# PCB_design.net
KiCad netlist of a schematic drawn in EAGLE
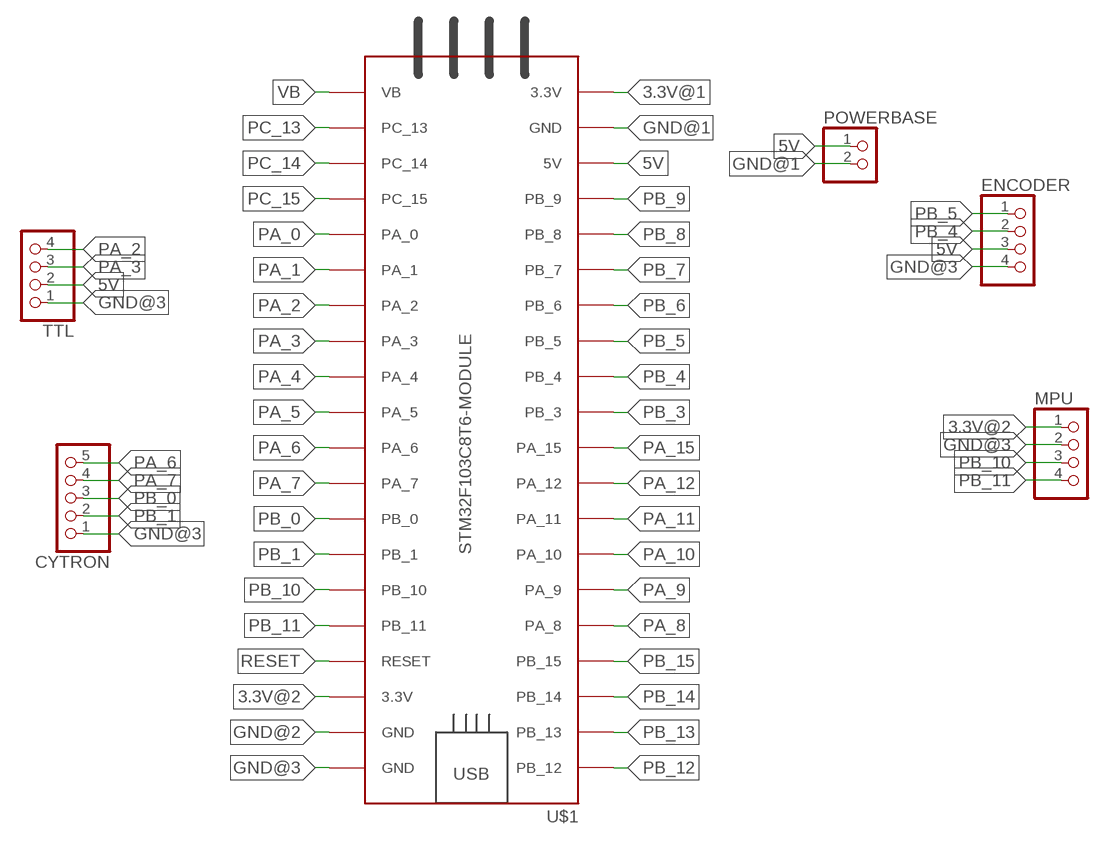
[diagram p0: schematic, sheet 1]

(export (version "E")
  (design (tool "Eeschema 10.0.6"))
  (components
    (comp (ref "CYTRON")
      (value "PINHD-1X5")
      (footprint "eagle-import:1X05")
      (libsource (lib "eagle-import") (part "PINHD-1X5"))
    )
    (comp (ref "ENCODER")
      (value "PINHD-1X4")
      (footprint "eagle-import:1X04")
      (libsource (lib "eagle-import") (part "PINHD-1X4"))
    )
    (comp (ref "MPU")
      (value "PINHD-1X4")
      (footprint "eagle-import:1X04")
      (libsource (lib "eagle-import") (part "PINHD-1X4"))
    )
    (comp (ref "POWERBASE")
      (value "PINHD-1X2")
      (footprint "eagle-import:1X02")
      (libsource (lib "eagle-import") (part "PINHD-1X2"))
    )
    (comp (ref "TTL")
      (value "PINHD-1X4")
      (footprint "eagle-import:1X04")
      (libsource (lib "eagle-import") (part "PINHD-1X4"))
    )
    (comp (ref "U$1")
      (value "STM32F103C8T6-MODULE")
      (footprint "eagle-import:STM32F103C8T6-MODULE")
      (libsource (lib "eagle-import") (part "STM32F103C8T6-MODULE"))
    )
  )
  (nets
    (net (code "1") (name "3.3V@1") (class "Default")
      (node (ref "U$1") (pin "3.3V_1") (pinfunction "3.3V_3.3V_1") (pintype "bidirectional"))
    )
    (net (code "2") (name "3.3V@2") (class "Default")
      (node (ref "MPU") (pin "1") (pinfunction "1_1") (pintype "passive"))
      (node (ref "U$1") (pin "3.3V_2") (pinfunction "3.3V_3.3V_2") (pintype "bidirectional"))
    )
    (net (code "3") (name "5V") (class "Default")
      (node (ref "ENCODER") (pin "3") (pinfunction "3_3") (pintype "passive"))
      (node (ref "POWERBASE") (pin "1") (pinfunction "1_1") (pintype "passive"))
      (node (ref "TTL") (pin "2") (pinfunction "2_2") (pintype "passive"))
      (node (ref "U$1") (pin "5V") (pinfunction "5V_5V") (pintype "bidirectional"))
    )
    (net (code "4") (name "GND@1") (class "Default")
      (node (ref "POWERBASE") (pin "2") (pinfunction "2_2") (pintype "passive"))
      (node (ref "U$1") (pin "GND_1") (pinfunction "GND_GND_1") (pintype "bidirectional"))
    )
    (net (code "5") (name "GND@2") (class "Default")
      (node (ref "U$1") (pin "GND_2") (pinfunction "GND_GND_2") (pintype "bidirectional"))
    )
    (net (code "6") (name "GND@3") (class "Default")
      (node (ref "CYTRON") (pin "1") (pinfunction "1_1") (pintype "passive"))
      (node (ref "ENCODER") (pin "4") (pinfunction "4_4") (pintype "passive"))
      (node (ref "MPU") (pin "2") (pinfunction "2_2") (pintype "passive"))
      (node (ref "TTL") (pin "1") (pinfunction "1_1") (pintype "passive"))
      (node (ref "U$1") (pin "GND_3") (pinfunction "GND_GND_3") (pintype "power_in"))
    )
    (net (code "7") (name "PA_0") (class "Default")
      (node (ref "U$1") (pin "PA_0") (pinfunction "PA_0_PA_0") (pintype "bidirectional"))
    )
    (net (code "8") (name "PA_1") (class "Default")
      (node (ref "U$1") (pin "PA_1") (pinfunction "PA_1_PA_1") (pintype "bidirectional"))
    )
    (net (code "9") (name "PA_2") (class "Default")
      (node (ref "TTL") (pin "4") (pinfunction "4_4") (pintype "passive"))
      (node (ref "U$1") (pin "PA_2") (pinfunction "PA_2_PA_2") (pintype "bidirectional"))
    )
    (net (code "10") (name "PA_3") (class "Default")
      (node (ref "TTL") (pin "3") (pinfunction "3_3") (pintype "passive"))
      (node (ref "U$1") (pin "PA_3") (pinfunction "PA_3_PA_3") (pintype "bidirectional"))
    )
    (net (code "11") (name "PA_4") (class "Default")
      (node (ref "U$1") (pin "PA_4") (pinfunction "PA_4_PA_4") (pintype "bidirectional"))
    )
    (net (code "12") (name "PA_5") (class "Default")
      (node (ref "U$1") (pin "PA_5") (pinfunction "PA_5_PA_5") (pintype "bidirectional"))
    )
    (net (code "13") (name "PA_6") (class "Default")
      (node (ref "CYTRON") (pin "5") (pinfunction "5_5") (pintype "passive"))
      (node (ref "U$1") (pin "PA_6") (pinfunction "PA_6_PA_6") (pintype "bidirectional"))
    )
    (net (code "14") (name "PA_7") (class "Default")
      (node (ref "CYTRON") (pin "4") (pinfunction "4_4") (pintype "passive"))
      (node (ref "U$1") (pin "PA_7") (pinfunction "PA_7_PA_7") (pintype "bidirectional"))
    )
    (net (code "15") (name "PA_8") (class "Default")
      (node (ref "U$1") (pin "PA_8") (pinfunction "PA_8_PA_8") (pintype "bidirectional"))
    )
    (net (code "16") (name "PA_9") (class "Default")
      (node (ref "U$1") (pin "PA_9") (pinfunction "PA_9_PA_9") (pintype "bidirectional"))
    )
    (net (code "17") (name "PA_10") (class "Default")
      (node (ref "U$1") (pin "PA_10") (pinfunction "PA_10_PA_10") (pintype "bidirectional"))
    )
    (net (code "18") (name "PA_11") (class "Default")
      (node (ref "U$1") (pin "PA_11") (pinfunction "PA_11_PA_11") (pintype "bidirectional"))
    )
    (net (code "19") (name "PA_12") (class "Default")
      (node (ref "U$1") (pin "PA_12") (pinfunction "PA_12_PA_12") (pintype "bidirectional"))
    )
    (net (code "20") (name "PA_15") (class "Default")
      (node (ref "U$1") (pin "PA_15") (pinfunction "PA_15_PA_15") (pintype "bidirectional"))
    )
    (net (code "21") (name "PB_0") (class "Default")
      (node (ref "CYTRON") (pin "3") (pinfunction "3_3") (pintype "passive"))
      (node (ref "U$1") (pin "PB_0") (pinfunction "PB_0_PB_0") (pintype "bidirectional"))
    )
    (net (code "22") (name "PB_1") (class "Default")
      (node (ref "CYTRON") (pin "2") (pinfunction "2_2") (pintype "passive"))
      (node (ref "U$1") (pin "PB_1") (pinfunction "PB_1_PB_1") (pintype "bidirectional"))
    )
    (net (code "23") (name "PB_3") (class "Default")
      (node (ref "U$1") (pin "PB_3") (pinfunction "PB_3_PB_3") (pintype "bidirectional"))
    )
    (net (code "24") (name "PB_4") (class "Default")
      (node (ref "ENCODER") (pin "2") (pinfunction "2_2") (pintype "passive"))
      (node (ref "U$1") (pin "PB_4") (pinfunction "PB_4_PB_4") (pintype "bidirectional"))
    )
    (net (code "25") (name "PB_5") (class "Default")
      (node (ref "ENCODER") (pin "1") (pinfunction "1_1") (pintype "passive"))
      (node (ref "U$1") (pin "PB_5") (pinfunction "PB_5_PB_5") (pintype "bidirectional"))
    )
    (net (code "26") (name "PB_6") (class "Default")
      (node (ref "U$1") (pin "PB_6") (pinfunction "PB_6_PB_6") (pintype "bidirectional"))
    )
    (net (code "27") (name "PB_7") (class "Default")
      (node (ref "U$1") (pin "PB_7") (pinfunction "PB_7_PB_7") (pintype "bidirectional"))
    )
    (net (code "28") (name "PB_8") (class "Default")
      (node (ref "U$1") (pin "PB_8") (pinfunction "PB_8_PB_8") (pintype "bidirectional"))
    )
    (net (code "29") (name "PB_9") (class "Default")
      (node (ref "U$1") (pin "PB_9") (pinfunction "PB_9_PB_9") (pintype "bidirectional"))
    )
    (net (code "30") (name "PB_10") (class "Default")
      (node (ref "MPU") (pin "3") (pinfunction "3_3") (pintype "passive"))
      (node (ref "U$1") (pin "PB_10") (pinfunction "PB_10_PB_10") (pintype "bidirectional"))
    )
    (net (code "31") (name "PB_11") (class "Default")
      (node (ref "MPU") (pin "4") (pinfunction "4_4") (pintype "passive"))
      (node (ref "U$1") (pin "PB_11") (pinfunction "PB_11_PB_11") (pintype "bidirectional"))
    )
    (net (code "32") (name "PB_12") (class "Default")
      (node (ref "U$1") (pin "PB_12") (pinfunction "PB_12_PB_12") (pintype "bidirectional"))
    )
    (net (code "33") (name "PB_13") (class "Default")
      (node (ref "U$1") (pin "PB_13") (pinfunction "PB_13_PB_13") (pintype "bidirectional"))
    )
    (net (code "34") (name "PB_14") (class "Default")
      (node (ref "U$1") (pin "PB_14") (pinfunction "PB_14_PB_14") (pintype "bidirectional"))
    )
    (net (code "35") (name "PB_15") (class "Default")
      (node (ref "U$1") (pin "PB_15") (pinfunction "PB_15_PB_15") (pintype "bidirectional"))
    )
    (net (code "36") (name "PC_13") (class "Default")
      (node (ref "U$1") (pin "PC_13") (pinfunction "PC_13_PC_13") (pintype "bidirectional"))
    )
    (net (code "37") (name "PC_14") (class "Default")
      (node (ref "U$1") (pin "PC_14") (pinfunction "PC_14_PC_14") (pintype "bidirectional"))
    )
    (net (code "38") (name "PC_15") (class "Default")
      (node (ref "U$1") (pin "PC_15") (pinfunction "PC_15_PC_15") (pintype "bidirectional"))
    )
    (net (code "39") (name "RESET") (class "Default")
      (node (ref "U$1") (pin "RESET") (pinfunction "RESET_RESET") (pintype "bidirectional"))
    )
    (net (code "40") (name "VB") (class "Default")
      (node (ref "U$1") (pin "VB") (pinfunction "VB_VB") (pintype "bidirectional"))
    )
  )
)
